# startum2.net
KiCad netlist of a schematic drawn in EAGLE
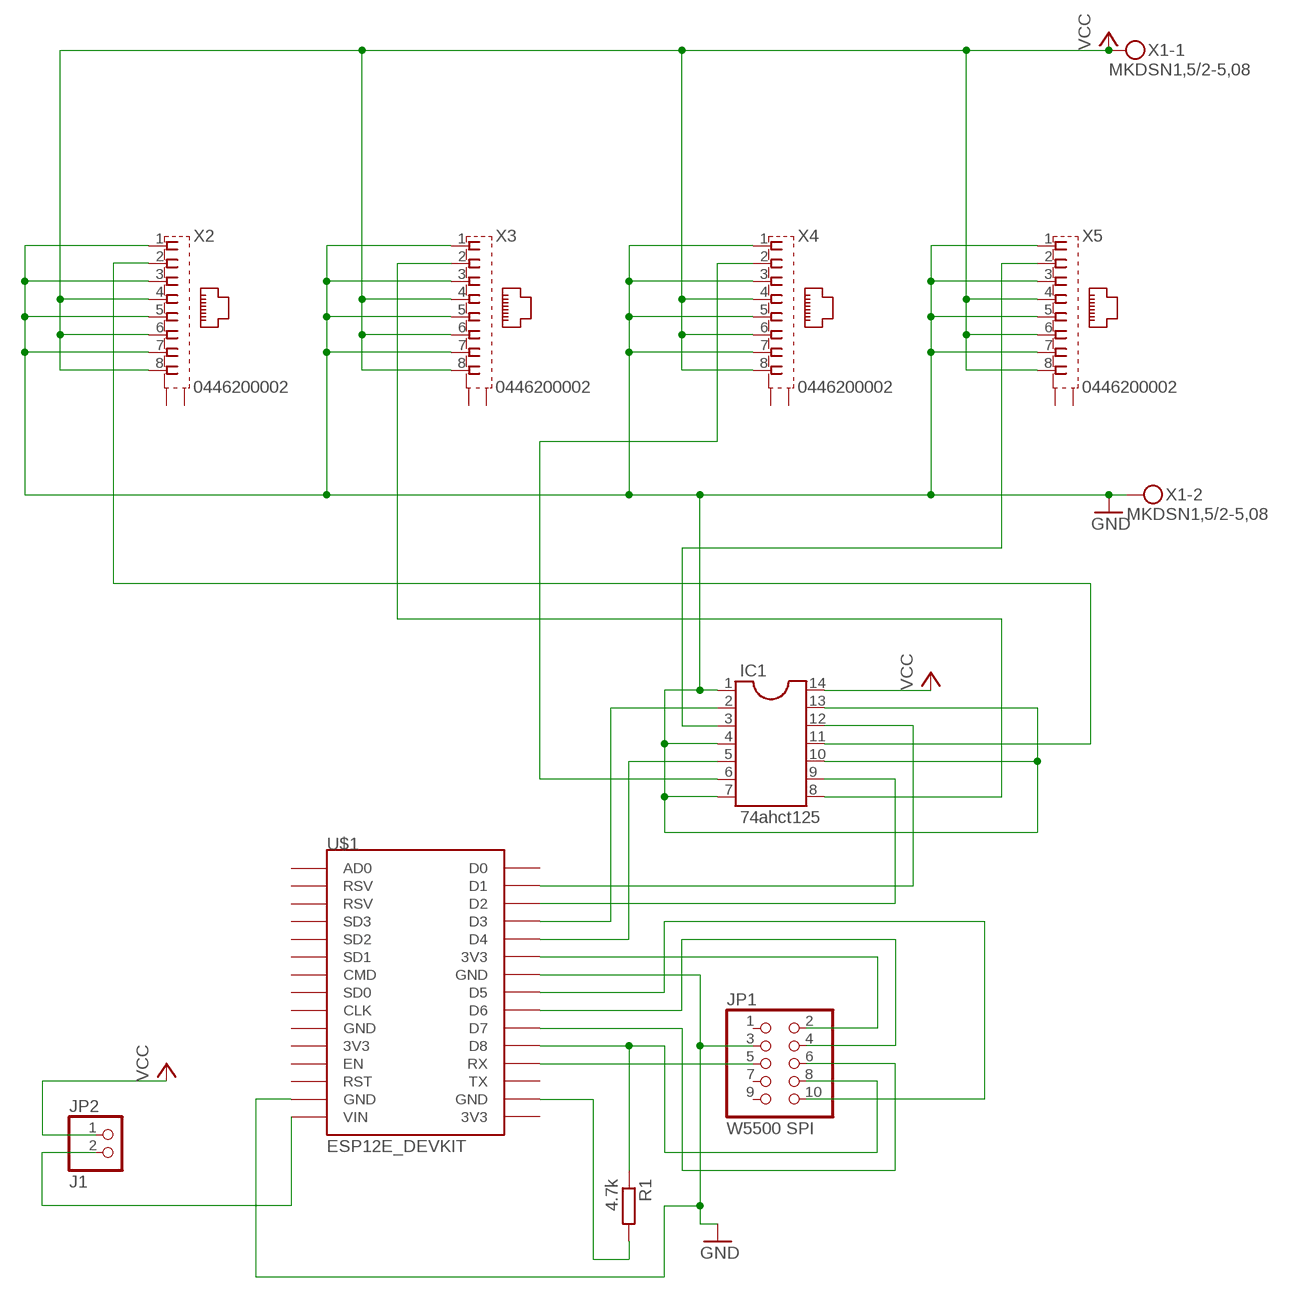
[diagram p0: schematic, sheet 1]

(export (version "E")
  (design (tool "Eeschema 10.0.6"))
  (components
    (comp (ref "IC1")
      (value "74ahct125")
      (footprint "eagle-import:DIL14")
      (fields (field (name "MF") "TEXAS INSTRUMENT CONNECTORS") (field (name "MPN") "SN74AHCT125N"))
      (libsource (lib "eagle-import") (part "DIL14"))
    )
    (comp (ref "JP1")
      (value "W5500 SPI")
      (footprint "eagle-import:2X05")
      (libsource (lib "eagle-import") (part "PINHD-2X5"))
    )
    (comp (ref "JP2")
      (value "J1")
      (footprint "eagle-import:1X02")
      (libsource (lib "eagle-import") (part "PINHD-1X2"))
    )
    (comp (ref "R1")
      (value "4.7k")
      (footprint "eagle-import:0207_10")
      (fields (field (name "MPN") "MCWF08P4701FTL"))
      (libsource (lib "eagle-import") (part "R-EU_0207/10"))
    )
    (comp (ref "U$1")
      (value "ESP12E_DEVKIT")
      (footprint "eagle-import:ESP12E_DEVKIT")
      (libsource (lib "eagle-import") (part "ESP12E_DEVKIT"))
    )
    (comp (ref "X1")
      (value "MKDSN1,5/2-5,08")
      (footprint "eagle-import:MKDSN1,5_2-5,08")
      (fields (field (name "OC_NEWARK") "unknown"))
      (libsource (lib "eagle-import") (part "MKDSN1,5/2-5,08"))
    )
    (comp (ref "X2")
      (value "0446200002")
      (footprint "eagle-import:0446200002")
      (fields (field (name "MF") "MOLEX") (field (name "MF_1") "FARNELL"))
      (libsource (lib "eagle-import") (part "0446200002"))
    )
    (comp (ref "X3")
      (value "0446200002")
      (footprint "eagle-import:0446200002")
      (fields (field (name "MF") "MOLEX") (field (name "MF_1") "FARNELL"))
      (libsource (lib "eagle-import") (part "0446200002"))
    )
    (comp (ref "X4")
      (value "0446200002")
      (footprint "eagle-import:0446200002")
      (fields (field (name "MF") "MOLEX") (field (name "MF_1") "FARNELL"))
      (libsource (lib "eagle-import") (part "0446200002"))
    )
    (comp (ref "X5")
      (value "0446200002")
      (footprint "eagle-import:0446200002")
      (fields (field (name "MF") "MOLEX") (field (name "MF_1") "FARNELL"))
      (libsource (lib "eagle-import") (part "0446200002"))
    )
  )
  (nets
    (net (code "1") (name "GND") (class "Default")
      (node (ref "IC1") (pin "1") (pinfunction "1_1") (pintype "passive"))
      (node (ref "IC1") (pin "10") (pinfunction "10_10") (pintype "passive"))
      (node (ref "IC1") (pin "13") (pinfunction "13_13") (pintype "passive"))
      (node (ref "IC1") (pin "4") (pinfunction "4_4") (pintype "passive"))
      (node (ref "IC1") (pin "7") (pinfunction "7_7") (pintype "passive"))
      (node (ref "JP1") (pin "3") (pinfunction "3_3") (pintype "passive"))
      (node (ref "U$1") (pin "GND@1") (pinfunction "GND_GND@1") (pintype "bidirectional"))
      (node (ref "U$1") (pin "GND@2") (pinfunction "GND_GND@2") (pintype "bidirectional"))
      (node (ref "X1") (pin "2") (pinfunction "KL_2") (pintype "passive"))
      (node (ref "X2") (pin "1") (pinfunction "1_1") (pintype "passive"))
      (node (ref "X2") (pin "3") (pinfunction "3_3") (pintype "passive"))
      (node (ref "X2") (pin "5") (pinfunction "5_5") (pintype "passive"))
      (node (ref "X2") (pin "7") (pinfunction "7_7") (pintype "passive"))
      (node (ref "X3") (pin "1") (pinfunction "1_1") (pintype "passive"))
      (node (ref "X3") (pin "3") (pinfunction "3_3") (pintype "passive"))
      (node (ref "X3") (pin "5") (pinfunction "5_5") (pintype "passive"))
      (node (ref "X3") (pin "7") (pinfunction "7_7") (pintype "passive"))
      (node (ref "X4") (pin "1") (pinfunction "1_1") (pintype "passive"))
      (node (ref "X4") (pin "3") (pinfunction "3_3") (pintype "passive"))
      (node (ref "X4") (pin "5") (pinfunction "5_5") (pintype "passive"))
      (node (ref "X4") (pin "7") (pinfunction "7_7") (pintype "passive"))
      (node (ref "X5") (pin "1") (pinfunction "1_1") (pintype "passive"))
      (node (ref "X5") (pin "3") (pinfunction "3_3") (pintype "passive"))
      (node (ref "X5") (pin "5") (pinfunction "5_5") (pintype "passive"))
      (node (ref "X5") (pin "7") (pinfunction "7_7") (pintype "passive"))
    )
    (net (code "2") (name "Net-(IC1-Pad2)") (class "Default")
      (node (ref "IC1") (pin "2") (pinfunction "2_2") (pintype "passive"))
      (node (ref "U$1") (pin "D3") (pinfunction "D3_D3") (pintype "bidirectional"))
    )
    (net (code "3") (name "Net-(IC1-Pad3)") (class "Default")
      (node (ref "IC1") (pin "3") (pinfunction "3_3") (pintype "passive"))
      (node (ref "X5") (pin "2") (pinfunction "2_2") (pintype "passive"))
    )
    (net (code "4") (name "Net-(IC1-Pad5)") (class "Default")
      (node (ref "IC1") (pin "5") (pinfunction "5_5") (pintype "passive"))
      (node (ref "U$1") (pin "D4") (pinfunction "D4_D4") (pintype "bidirectional"))
    )
    (net (code "5") (name "Net-(IC1-Pad6)") (class "Default")
      (node (ref "IC1") (pin "6") (pinfunction "6_6") (pintype "passive"))
      (node (ref "X4") (pin "2") (pinfunction "2_2") (pintype "passive"))
    )
    (net (code "6") (name "Net-(IC1-Pad8)") (class "Default")
      (node (ref "IC1") (pin "8") (pinfunction "8_8") (pintype "passive"))
      (node (ref "X3") (pin "2") (pinfunction "2_2") (pintype "passive"))
    )
    (net (code "7") (name "Net-(IC1-Pad9)") (class "Default")
      (node (ref "IC1") (pin "9") (pinfunction "9_9") (pintype "passive"))
      (node (ref "U$1") (pin "D2") (pinfunction "D2_D2") (pintype "bidirectional"))
    )
    (net (code "8") (name "Net-(IC1-Pad11)") (class "Default")
      (node (ref "IC1") (pin "11") (pinfunction "11_11") (pintype "passive"))
      (node (ref "X2") (pin "2") (pinfunction "2_2") (pintype "passive"))
    )
    (net (code "9") (name "Net-(IC1-Pad12)") (class "Default")
      (node (ref "IC1") (pin "12") (pinfunction "12_12") (pintype "passive"))
      (node (ref "U$1") (pin "D1") (pinfunction "D1_D1") (pintype "bidirectional"))
    )
    (net (code "10") (name "Net-(JP1-Pad2)") (class "Default")
      (node (ref "JP1") (pin "2") (pinfunction "2_2") (pintype "passive"))
      (node (ref "U$1") (pin "3V3@1") (pinfunction "3V3_3V3@1") (pintype "bidirectional"))
    )
    (net (code "11") (name "Net-(JP1-Pad4)") (class "Default")
      (node (ref "JP1") (pin "4") (pinfunction "4_4") (pintype "passive"))
      (node (ref "U$1") (pin "D6") (pinfunction "D6_D6") (pintype "bidirectional"))
    )
    (net (code "12") (name "Net-(JP1-Pad5)") (class "Default")
      (node (ref "JP1") (pin "5") (pinfunction "5_5") (pintype "passive"))
      (node (ref "U$1") (pin "RX") (pinfunction "RX_RX") (pintype "bidirectional"))
    )
    (net (code "13") (name "Net-(JP1-Pad6)") (class "Default")
      (node (ref "JP1") (pin "6") (pinfunction "6_6") (pintype "passive"))
      (node (ref "U$1") (pin "D7") (pinfunction "D7_D7") (pintype "bidirectional"))
    )
    (net (code "14") (name "Net-(JP1-Pad8)") (class "Default")
      (node (ref "JP1") (pin "8") (pinfunction "8_8") (pintype "passive"))
      (node (ref "R1") (pin "1") (pinfunction "1_1") (pintype "passive"))
      (node (ref "U$1") (pin "D8") (pinfunction "D8_D8") (pintype "bidirectional"))
    )
    (net (code "15") (name "Net-(JP1-Pad10)") (class "Default")
      (node (ref "JP1") (pin "10") (pinfunction "10_10") (pintype "passive"))
      (node (ref "U$1") (pin "D5") (pinfunction "D5_D5") (pintype "bidirectional"))
    )
    (net (code "16") (name "Net-(JP2-Pad2)") (class "Default")
      (node (ref "JP2") (pin "2") (pinfunction "2_2") (pintype "passive"))
      (node (ref "U$1") (pin "VIN") (pinfunction "VIN_VIN") (pintype "bidirectional"))
    )
    (net (code "17") (name "Net-(R1-Pad2)") (class "Default")
      (node (ref "R1") (pin "2") (pinfunction "2_2") (pintype "passive"))
      (node (ref "U$1") (pin "GND@3") (pinfunction "GND_GND@3") (pintype "bidirectional"))
    )
    (net (code "18") (name "VCC") (class "Default")
      (node (ref "IC1") (pin "14") (pinfunction "14_14") (pintype "passive"))
      (node (ref "JP2") (pin "1") (pinfunction "1_1") (pintype "passive"))
      (node (ref "X1") (pin "1") (pinfunction "KL_1") (pintype "passive"))
      (node (ref "X2") (pin "4") (pinfunction "4_4") (pintype "passive"))
      (node (ref "X2") (pin "6") (pinfunction "6_6") (pintype "passive"))
      (node (ref "X2") (pin "8") (pinfunction "8_8") (pintype "passive"))
      (node (ref "X3") (pin "4") (pinfunction "4_4") (pintype "passive"))
      (node (ref "X3") (pin "6") (pinfunction "6_6") (pintype "passive"))
      (node (ref "X3") (pin "8") (pinfunction "8_8") (pintype "passive"))
      (node (ref "X4") (pin "4") (pinfunction "4_4") (pintype "passive"))
      (node (ref "X4") (pin "6") (pinfunction "6_6") (pintype "passive"))
      (node (ref "X4") (pin "8") (pinfunction "8_8") (pintype "passive"))
      (node (ref "X5") (pin "4") (pinfunction "4_4") (pintype "passive"))
      (node (ref "X5") (pin "6") (pinfunction "6_6") (pintype "passive"))
      (node (ref "X5") (pin "8") (pinfunction "8_8") (pintype "passive"))
    )
    (net (code "19") (name "unconnected-(JP1-Pad1)") (class "Default")
      (node (ref "JP1") (pin "1") (pinfunction "1_1") (pintype "passive"))
    )
    (net (code "20") (name "unconnected-(JP1-Pad7)") (class "Default")
      (node (ref "JP1") (pin "7") (pinfunction "7_7") (pintype "passive"))
    )
    (net (code "21") (name "unconnected-(JP1-Pad9)") (class "Default")
      (node (ref "JP1") (pin "9") (pinfunction "9_9") (pintype "passive"))
    )
    (net (code "22") (name "unconnected-(U$1-3V3-Pad3V3@0)") (class "Default")
      (node (ref "U$1") (pin "3V3@0") (pinfunction "3V3_3V3@0") (pintype "bidirectional"))
    )
    (net (code "23") (name "unconnected-(U$1-3V3-Pad3V3@2)") (class "Default")
      (node (ref "U$1") (pin "3V3@2") (pinfunction "3V3_3V3@2") (pintype "bidirectional"))
    )
    (net (code "24") (name "unconnected-(U$1-GND-PadGND@0)") (class "Default")
      (node (ref "U$1") (pin "GND@0") (pinfunction "GND_GND@0") (pintype "bidirectional"))
    )
    (net (code "25") (name "unconnected-(U$1-PadAD0)") (class "Default")
      (node (ref "U$1") (pin "AD0") (pinfunction "AD0_AD0") (pintype "bidirectional"))
    )
    (net (code "26") (name "unconnected-(U$1-PadCLK)") (class "Default")
      (node (ref "U$1") (pin "CLK") (pinfunction "CLK_CLK") (pintype "bidirectional"))
    )
    (net (code "27") (name "unconnected-(U$1-PadCMD)") (class "Default")
      (node (ref "U$1") (pin "CMD") (pinfunction "CMD_CMD") (pintype "bidirectional"))
    )
    (net (code "28") (name "unconnected-(U$1-PadD0)") (class "Default")
      (node (ref "U$1") (pin "D0") (pinfunction "D0_D0") (pintype "bidirectional"))
    )
    (net (code "29") (name "unconnected-(U$1-PadEN)") (class "Default")
      (node (ref "U$1") (pin "EN") (pinfunction "EN_EN") (pintype "bidirectional"))
    )
    (net (code "30") (name "unconnected-(U$1-PadRST)") (class "Default")
      (node (ref "U$1") (pin "RST") (pinfunction "RST_RST") (pintype "bidirectional"))
    )
    (net (code "31") (name "unconnected-(U$1-PadSD0)") (class "Default")
      (node (ref "U$1") (pin "SD0") (pinfunction "SD0_SD0") (pintype "bidirectional"))
    )
    (net (code "32") (name "unconnected-(U$1-PadSD1)") (class "Default")
      (node (ref "U$1") (pin "SD1") (pinfunction "SD1_SD1") (pintype "bidirectional"))
    )
    (net (code "33") (name "unconnected-(U$1-PadSD2)") (class "Default")
      (node (ref "U$1") (pin "SD2") (pinfunction "SD2_SD2") (pintype "bidirectional"))
    )
    (net (code "34") (name "unconnected-(U$1-PadSD3)") (class "Default")
      (node (ref "U$1") (pin "SD3") (pinfunction "SD3_SD3") (pintype "bidirectional"))
    )
    (net (code "35") (name "unconnected-(U$1-PadTX)") (class "Default")
      (node (ref "U$1") (pin "TX") (pinfunction "TX_TX") (pintype "bidirectional"))
    )
    (net (code "36") (name "unconnected-(U$1-RSV-PadRSV@0)") (class "Default")
      (node (ref "U$1") (pin "RSV@0") (pinfunction "RSV_RSV@0") (pintype "bidirectional"))
    )
    (net (code "37") (name "unconnected-(U$1-RSV-PadRSV@1)") (class "Default")
      (node (ref "U$1") (pin "RSV@1") (pinfunction "RSV_RSV@1") (pintype "bidirectional"))
    )
    (net (code "38") (name "unconnected-(X2-S1-PadS@1)") (class "Default")
      (node (ref "X2") (pin "S@1") (pinfunction "S1_S@1") (pintype "passive"))
    )
    (net (code "39") (name "unconnected-(X2-S2-PadS@2)") (class "Default")
      (node (ref "X2") (pin "S@2") (pinfunction "S2_S@2") (pintype "passive"))
    )
    (net (code "40") (name "unconnected-(X3-S1-PadS@1)") (class "Default")
      (node (ref "X3") (pin "S@1") (pinfunction "S1_S@1") (pintype "passive"))
    )
    (net (code "41") (name "unconnected-(X3-S2-PadS@2)") (class "Default")
      (node (ref "X3") (pin "S@2") (pinfunction "S2_S@2") (pintype "passive"))
    )
    (net (code "42") (name "unconnected-(X4-S1-PadS@1)") (class "Default")
      (node (ref "X4") (pin "S@1") (pinfunction "S1_S@1") (pintype "passive"))
    )
    (net (code "43") (name "unconnected-(X4-S2-PadS@2)") (class "Default")
      (node (ref "X4") (pin "S@2") (pinfunction "S2_S@2") (pintype "passive"))
    )
    (net (code "44") (name "unconnected-(X5-S1-PadS@1)") (class "Default")
      (node (ref "X5") (pin "S@1") (pinfunction "S1_S@1") (pintype "passive"))
    )
    (net (code "45") (name "unconnected-(X5-S2-PadS@2)") (class "Default")
      (node (ref "X5") (pin "S@2") (pinfunction "S2_S@2") (pintype "passive"))
    )
  )
)
